# ddr3.net
KiCad netlist of a schematic drawn in Altium Designer
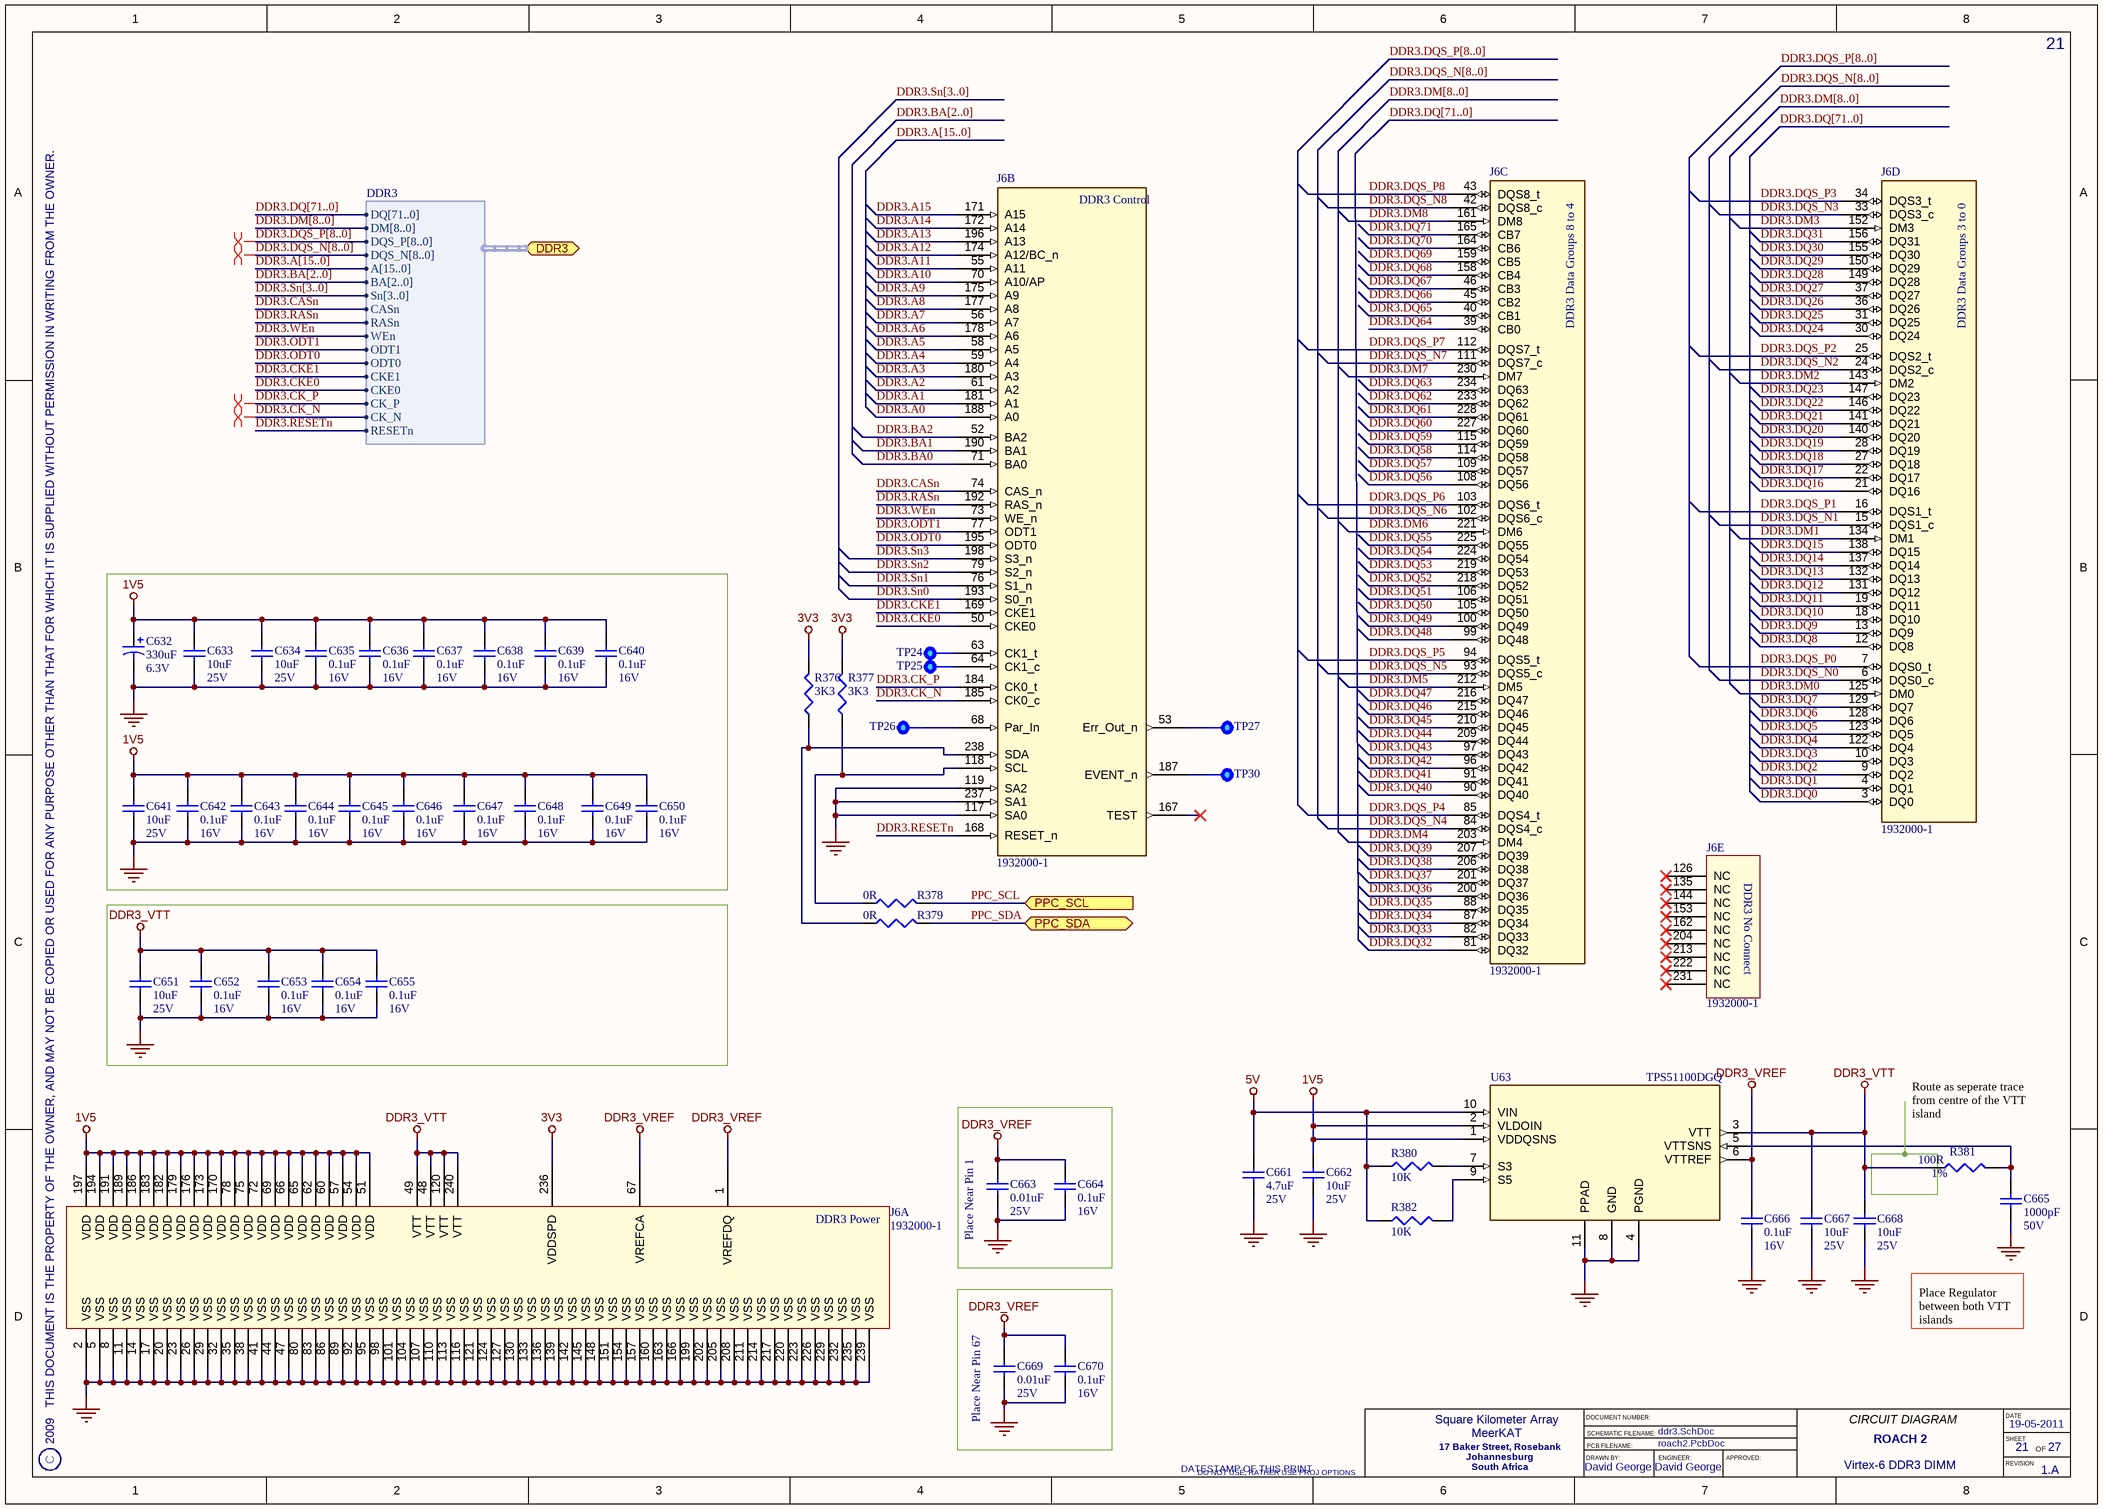
[diagram p0: ddr3.SchDoc]

(export (version "E")
  (design (tool "Eeschema 10.0.6"))
  (components
    (comp (ref "C632")
      (value "330uF")
      (footprint "CAPMP7343X280L")
      (description "330uF, Conductive Polymer Chip Capacitor")
      (fields
        (field (name "RATING") "6.3V")
        (field (name "MANUFACTURER") "KEMET")
        (field (name "PARTNUM") "T520D337M006ATE045")
      )
      (libsource (lib "altium_db") (part "CapPol"))
    )
    (comp (ref "C633")
      (value "10uF")
      (footprint "CAPC3225X200L")
      (description "10uF, Ceramic Capacitor")
      (fields
        (field (name "RATING") "25V")
        (field (name "MANUFACTURER") "MURATA")
        (field (name "PARTNUM") "GRM32DR61E106KA12L")
      )
      (libsource (lib "altium_db") (part "CapStd"))
    )
    (comp (ref "C634")
      (value "10uF")
      (footprint "CAPC3225X200L")
      (description "10uF, Ceramic Capacitor")
      (fields
        (field (name "RATING") "25V")
        (field (name "MANUFACTURER") "MURATA")
        (field (name "PARTNUM") "GRM32DR61E106KA12L")
      )
      (libsource (lib "altium_db") (part "CapStd"))
    )
    (comp (ref "C635")
      (value "0.1uF")
      (footprint "CAPC1005X60L")
      (description "0.1uF, Ceramic Capacitor")
      (fields
        (field (name "RATING") "16V")
        (field (name "MANUFACTURER") "VENKEL")
        (field (name "PARTNUM") "C0402X7R160-104KN")
      )
      (libsource (lib "altium_db") (part "CapStd"))
    )
    (comp (ref "C636")
      (value "0.1uF")
      (footprint "CAPC1005X60L")
      (description "0.1uF, Ceramic Capacitor")
      (fields
        (field (name "RATING") "16V")
        (field (name "MANUFACTURER") "VENKEL")
        (field (name "PARTNUM") "C0402X7R160-104KN")
      )
      (libsource (lib "altium_db") (part "CapStd"))
    )
    (comp (ref "C637")
      (value "0.1uF")
      (footprint "CAPC1005X60L")
      (description "0.1uF, Ceramic Capacitor")
      (fields
        (field (name "RATING") "16V")
        (field (name "MANUFACTURER") "VENKEL")
        (field (name "PARTNUM") "C0402X7R160-104KN")
      )
      (libsource (lib "altium_db") (part "CapStd"))
    )
    (comp (ref "C638")
      (value "0.1uF")
      (footprint "CAPC1005X60L")
      (description "0.1uF, Ceramic Capacitor")
      (fields
        (field (name "RATING") "16V")
        (field (name "MANUFACTURER") "VENKEL")
        (field (name "PARTNUM") "C0402X7R160-104KN")
      )
      (libsource (lib "altium_db") (part "CapStd"))
    )
    (comp (ref "C639")
      (value "0.1uF")
      (footprint "CAPC1005X60L")
      (description "0.1uF, Ceramic Capacitor")
      (fields
        (field (name "RATING") "16V")
        (field (name "MANUFACTURER") "VENKEL")
        (field (name "PARTNUM") "C0402X7R160-104KN")
      )
      (libsource (lib "altium_db") (part "CapStd"))
    )
    (comp (ref "C640")
      (value "0.1uF")
      (footprint "CAPC1005X60L")
      (description "0.1uF, Ceramic Capacitor")
      (fields
        (field (name "RATING") "16V")
        (field (name "MANUFACTURER") "VENKEL")
        (field (name "PARTNUM") "C0402X7R160-104KN")
      )
      (libsource (lib "altium_db") (part "CapStd"))
    )
    (comp (ref "C641")
      (value "10uF")
      (footprint "CAPC3225X200L")
      (description "10uF, Ceramic Capacitor")
      (fields
        (field (name "RATING") "25V")
        (field (name "MANUFACTURER") "MURATA")
        (field (name "PARTNUM") "GRM32DR61E106KA12L")
      )
      (libsource (lib "altium_db") (part "CapStd"))
    )
    (comp (ref "C642")
      (value "0.1uF")
      (footprint "CAPC1005X60L")
      (description "0.1uF, Ceramic Capacitor")
      (fields
        (field (name "RATING") "16V")
        (field (name "MANUFACTURER") "VENKEL")
        (field (name "PARTNUM") "C0402X7R160-104KN")
      )
      (libsource (lib "altium_db") (part "CapStd"))
    )
    (comp (ref "C643")
      (value "0.1uF")
      (footprint "CAPC1005X60L")
      (description "0.1uF, Ceramic Capacitor")
      (fields
        (field (name "RATING") "16V")
        (field (name "MANUFACTURER") "VENKEL")
        (field (name "PARTNUM") "C0402X7R160-104KN")
      )
      (libsource (lib "altium_db") (part "CapStd"))
    )
    (comp (ref "C644")
      (value "0.1uF")
      (footprint "CAPC1005X60L")
      (description "0.1uF, Ceramic Capacitor")
      (fields
        (field (name "RATING") "16V")
        (field (name "MANUFACTURER") "VENKEL")
        (field (name "PARTNUM") "C0402X7R160-104KN")
      )
      (libsource (lib "altium_db") (part "CapStd"))
    )
    (comp (ref "C645")
      (value "0.1uF")
      (footprint "CAPC1005X60L")
      (description "0.1uF, Ceramic Capacitor")
      (fields
        (field (name "RATING") "16V")
        (field (name "MANUFACTURER") "VENKEL")
        (field (name "PARTNUM") "C0402X7R160-104KN")
      )
      (libsource (lib "altium_db") (part "CapStd"))
    )
    (comp (ref "C646")
      (value "0.1uF")
      (footprint "CAPC1005X60L")
      (description "0.1uF, Ceramic Capacitor")
      (fields
        (field (name "RATING") "16V")
        (field (name "MANUFACTURER") "VENKEL")
        (field (name "PARTNUM") "C0402X7R160-104KN")
      )
      (libsource (lib "altium_db") (part "CapStd"))
    )
    (comp (ref "C647")
      (value "0.1uF")
      (footprint "CAPC1005X60L")
      (description "0.1uF, Ceramic Capacitor")
      (fields
        (field (name "RATING") "16V")
        (field (name "MANUFACTURER") "VENKEL")
        (field (name "PARTNUM") "C0402X7R160-104KN")
      )
      (libsource (lib "altium_db") (part "CapStd"))
    )
    (comp (ref "C648")
      (value "0.1uF")
      (footprint "CAPC1005X60L")
      (description "0.1uF, Ceramic Capacitor")
      (fields
        (field (name "RATING") "16V")
        (field (name "MANUFACTURER") "VENKEL")
        (field (name "PARTNUM") "C0402X7R160-104KN")
      )
      (libsource (lib "altium_db") (part "CapStd"))
    )
    (comp (ref "C649")
      (value "0.1uF")
      (footprint "CAPC1005X60L")
      (description "0.1uF, Ceramic Capacitor")
      (fields
        (field (name "RATING") "16V")
        (field (name "MANUFACTURER") "VENKEL")
        (field (name "PARTNUM") "C0402X7R160-104KN")
      )
      (libsource (lib "altium_db") (part "CapStd"))
    )
    (comp (ref "C650")
      (value "0.1uF")
      (footprint "CAPC1005X60L")
      (description "0.1uF, Ceramic Capacitor")
      (fields
        (field (name "RATING") "16V")
        (field (name "MANUFACTURER") "VENKEL")
        (field (name "PARTNUM") "C0402X7R160-104KN")
      )
      (libsource (lib "altium_db") (part "CapStd"))
    )
    (comp (ref "C651")
      (value "10uF")
      (footprint "CAPC3225X200L")
      (description "10uF, Ceramic Capacitor")
      (fields
        (field (name "RATING") "25V")
        (field (name "MANUFACTURER") "MURATA")
        (field (name "PARTNUM") "GRM32DR61E106KA12L")
      )
      (libsource (lib "altium_db") (part "CapStd"))
    )
    (comp (ref "C652")
      (value "0.1uF")
      (footprint "CAPC1005X60L")
      (description "0.1uF, Ceramic Capacitor")
      (fields
        (field (name "RATING") "16V")
        (field (name "MANUFACTURER") "VENKEL")
        (field (name "PARTNUM") "C0402X7R160-104KN")
      )
      (libsource (lib "altium_db") (part "CapStd"))
    )
    (comp (ref "C653")
      (value "0.1uF")
      (footprint "CAPC1005X60L")
      (description "0.1uF, Ceramic Capacitor")
      (fields
        (field (name "RATING") "16V")
        (field (name "MANUFACTURER") "VENKEL")
        (field (name "PARTNUM") "C0402X7R160-104KN")
      )
      (libsource (lib "altium_db") (part "CapStd"))
    )
    (comp (ref "C654")
      (value "0.1uF")
      (footprint "CAPC1005X60L")
      (description "0.1uF, Ceramic Capacitor")
      (fields
        (field (name "RATING") "16V")
        (field (name "MANUFACTURER") "VENKEL")
        (field (name "PARTNUM") "C0402X7R160-104KN")
      )
      (libsource (lib "altium_db") (part "CapStd"))
    )
    (comp (ref "C655")
      (value "0.1uF")
      (footprint "CAPC1005X60L")
      (description "0.1uF, Ceramic Capacitor")
      (fields
        (field (name "RATING") "16V")
        (field (name "MANUFACTURER") "VENKEL")
        (field (name "PARTNUM") "C0402X7R160-104KN")
      )
      (libsource (lib "altium_db") (part "CapStd"))
    )
    (comp (ref "C661")
      (value "4.7uF")
      (footprint "CAPC2012X127L")
      (description "4.7uF, Ceramic Capacitor")
      (fields
        (field (name "RATING") "25V")
        (field (name "MANUFACTURER") "MURATA")
        (field (name "PARTNUM") "GRM21BR61E475KA12K")
      )
      (libsource (lib "altium_db") (part "CapStd"))
    )
    (comp (ref "C662")
      (value "10uF")
      (footprint "CAPC3225X200L")
      (description "10uF, Ceramic Capacitor")
      (fields
        (field (name "RATING") "25V")
        (field (name "MANUFACTURER") "MURATA")
        (field (name "PARTNUM") "GRM32DR61E106KA12L")
      )
      (libsource (lib "altium_db") (part "CapStd"))
    )
    (comp (ref "C663")
      (value "0.01uF")
      (footprint "CAPC1005X55L")
      (description "0.01uF, Ceramic Capacitor")
      (fields
        (field (name "RATING") "25V")
        (field (name "MANUFACTURER") "MURATA")
        (field (name "PARTNUM") "GRM155R71E103KA01D")
      )
      (libsource (lib "altium_db") (part "CapStd"))
    )
    (comp (ref "C664")
      (value "0.1uF")
      (footprint "CAPC1005X60L")
      (description "0.1uF, Ceramic Capacitor")
      (fields
        (field (name "RATING") "16V")
        (field (name "MANUFACTURER") "VENKEL")
        (field (name "PARTNUM") "C0402X7R160-104KN")
      )
      (libsource (lib "altium_db") (part "CapStd"))
    )
    (comp (ref "C665")
      (value "1000pF")
      (footprint "CAPC1005X55L")
      (description "1000pF, Ceramic Capacitor")
      (fields
        (field (name "RATING") "50V")
        (field (name "MANUFACTURER") "MURATA")
        (field (name "PARTNUM") "GRM155R61H102KA01D")
      )
      (libsource (lib "altium_db") (part "CapStd"))
    )
    (comp (ref "C666")
      (value "0.1uF")
      (footprint "CAPC1005X60L")
      (description "0.1uF, Ceramic Capacitor")
      (fields
        (field (name "RATING") "16V")
        (field (name "MANUFACTURER") "VENKEL")
        (field (name "PARTNUM") "C0402X7R160-104KN")
      )
      (libsource (lib "altium_db") (part "CapStd"))
    )
    (comp (ref "C667")
      (value "10uF")
      (footprint "CAPC3225X200L")
      (description "10uF, Ceramic Capacitor")
      (fields
        (field (name "RATING") "25V")
        (field (name "MANUFACTURER") "MURATA")
        (field (name "PARTNUM") "GRM32DR61E106KA12L")
      )
      (libsource (lib "altium_db") (part "CapStd"))
    )
    (comp (ref "C668")
      (value "10uF")
      (footprint "CAPC3225X200L")
      (description "10uF, Ceramic Capacitor")
      (fields
        (field (name "RATING") "25V")
        (field (name "MANUFACTURER") "MURATA")
        (field (name "PARTNUM") "GRM32DR61E106KA12L")
      )
      (libsource (lib "altium_db") (part "CapStd"))
    )
    (comp (ref "C669")
      (value "0.01uF")
      (footprint "CAPC1005X55L")
      (description "0.01uF, Ceramic Capacitor")
      (fields
        (field (name "RATING") "25V")
        (field (name "MANUFACTURER") "MURATA")
        (field (name "PARTNUM") "GRM155R71E103KA01D")
      )
      (libsource (lib "altium_db") (part "CapStd"))
    )
    (comp (ref "C670")
      (value "0.1uF")
      (footprint "CAPC1005X60L")
      (description "0.1uF, Ceramic Capacitor")
      (fields
        (field (name "RATING") "16V")
        (field (name "MANUFACTURER") "VENKEL")
        (field (name "PARTNUM") "C0402X7R160-104KN")
      )
      (libsource (lib "altium_db") (part "CapStd"))
    )
    (comp (ref "J6")
      (value "1932000-1")
      (footprint "TYCO_1932000-1")
      (description "240-pin DDR3 DIMM Socket")
      (fields (field (name "PARTNUM") "1932000-1") (field (name "MANUFACTURER") "TYCO"))
      (libsource (lib "altium_db") (part "ddr3_dimm_240"))
    )
    (comp (ref "R376")
      (value "3K3")
      (footprint "RESC1005X40L")
      (description "3K3, 1.1mm x 0.5mm, Thick Film Resistor")
      (fields (field (name "MANUFACTURER") "ROYALOHM") (field (name "PARTNUM") "0402WGJ0332T1E"))
      (libsource (lib "altium_db") (part "ResStd"))
    )
    (comp (ref "R377")
      (value "3K3")
      (footprint "RESC1005X40L")
      (description "3K3, 1.1mm x 0.5mm, Thick Film Resistor")
      (fields (field (name "MANUFACTURER") "ROYALOHM") (field (name "PARTNUM") "0402WGJ0332T1E"))
      (libsource (lib "altium_db") (part "ResStd"))
    )
    (comp (ref "R378")
      (value "0R")
      (footprint "RESC1005X40L")
      (description "0R, 1.1mm x 0.5mm, Thick Film Resistor")
      (fields (field (name "MANUFACTURER") "ROYALOHM") (field (name "PARTNUM") "0402WG00000T1E"))
      (libsource (lib "altium_db") (part "ResStd"))
    )
    (comp (ref "R379")
      (value "0R")
      (footprint "RESC1005X40L")
      (description "0R, 1.1mm x 0.5mm, Thick Film Resistor")
      (fields (field (name "MANUFACTURER") "ROYALOHM") (field (name "PARTNUM") "0402WG00000T1E"))
      (libsource (lib "altium_db") (part "ResStd"))
    )
    (comp (ref "R380")
      (value "10K")
      (footprint "RESC1005X40L")
      (description "10K, 1.1mm x 0.5mm, Thick Film Resistor")
      (fields (field (name "MANUFACTURER") "ROYALOHM") (field (name "PARTNUM") "0402WGJ0103T1E"))
      (libsource (lib "altium_db") (part "ResStd"))
    )
    (comp (ref "R381")
      (value "100R")
      (footprint "RESC1005X40L")
      (description "100R, 1.1mm x 0.5mm, Thick Film Resistor")
      (fields
        (field (name "MANUFACTURER") "ROYALOHM")
        (field (name "PARTNUM") "0402WGF0101T1E")
        (field (name "TOLERANCE") "1%")
      )
      (libsource (lib "altium_db") (part "ResStd"))
    )
    (comp (ref "R382")
      (value "10K")
      (footprint "RESC1005X40L")
      (description "10K, 1.1mm x 0.5mm, Thick Film Resistor")
      (fields (field (name "MANUFACTURER") "ROYALOHM") (field (name "PARTNUM") "0402WGJ0103T1E"))
      (libsource (lib "altium_db") (part "ResStd"))
    )
    (comp (ref "TP24")
      (value "Testpoint")
      (footprint "TP100")
      (description "1mm Diameter, through-hole, Circular Test-point")
      (libsource (lib "altium_db") (part "Testpoint"))
    )
    (comp (ref "TP25")
      (value "Testpoint")
      (footprint "TP100")
      (description "1mm Diameter, through-hole, Circular Test-point")
      (libsource (lib "altium_db") (part "Testpoint"))
    )
    (comp (ref "TP26")
      (value "Testpoint")
      (footprint "TP100")
      (description "1mm Diameter, through-hole, Circular Test-point")
      (libsource (lib "altium_db") (part "Testpoint"))
    )
    (comp (ref "TP27")
      (value "Testpoint")
      (footprint "TP100")
      (description "1mm Diameter, through-hole, Circular Test-point")
      (libsource (lib "altium_db") (part "Testpoint"))
    )
    (comp (ref "TP30")
      (value "Testpoint")
      (footprint "TP100")
      (description "1mm Diameter, through-hole, Circular Test-point")
      (libsource (lib "altium_db") (part "Testpoint"))
    )
    (comp (ref "U63")
      (value "TPS51100DGQ")
      (footprint "MSOP_10-N")
      (description "3A Sink/Source Regulator")
      (fields (field (name "MANUFACTURER") "Texas Instruments"))
      (libsource (lib "altium_db") (part "TPS51100DGQ"))
    )
  )
  (nets
    (net (code "2") (name "/DDR3.A0") (class "Default")
      (node (ref "J6") (pin "188") (pinfunction "A0_188") (pintype "input"))
    )
    (net (code "3") (name "/DDR3.A1") (class "Default")
      (node (ref "J6") (pin "181") (pinfunction "A1_181") (pintype "input"))
    )
    (net (code "4") (name "/DDR3.A2") (class "Default")
      (node (ref "J6") (pin "61") (pinfunction "A2_61") (pintype "input"))
    )
    (net (code "5") (name "/DDR3.A3") (class "Default")
      (node (ref "J6") (pin "180") (pinfunction "A3_180") (pintype "input"))
    )
    (net (code "6") (name "/DDR3.A4") (class "Default")
      (node (ref "J6") (pin "59") (pinfunction "A4_59") (pintype "input"))
    )
    (net (code "7") (name "/DDR3.A5") (class "Default")
      (node (ref "J6") (pin "58") (pinfunction "A5_58") (pintype "input"))
    )
    (net (code "8") (name "/DDR3.A6") (class "Default")
      (node (ref "J6") (pin "178") (pinfunction "A6_178") (pintype "input"))
    )
    (net (code "9") (name "/DDR3.A7") (class "Default")
      (node (ref "J6") (pin "56") (pinfunction "A7_56") (pintype "input"))
    )
    (net (code "10") (name "/DDR3.A8") (class "Default")
      (node (ref "J6") (pin "177") (pinfunction "A8_177") (pintype "input"))
    )
    (net (code "11") (name "/DDR3.A9") (class "Default")
      (node (ref "J6") (pin "175") (pinfunction "A9_175") (pintype "input"))
    )
    (net (code "12") (name "/DDR3.A10") (class "Default")
      (node (ref "J6") (pin "70") (pinfunction "A10/AP_70") (pintype "input"))
    )
    (net (code "13") (name "/DDR3.A11") (class "Default")
      (node (ref "J6") (pin "55") (pinfunction "A11_55") (pintype "input"))
    )
    (net (code "14") (name "/DDR3.A12") (class "Default")
      (node (ref "J6") (pin "174") (pinfunction "A12/BC_n_174") (pintype "input"))
    )
    (net (code "15") (name "/DDR3.A13") (class "Default")
      (node (ref "J6") (pin "196") (pinfunction "A13_196") (pintype "input"))
    )
    (net (code "16") (name "/DDR3.A14") (class "Default")
      (node (ref "J6") (pin "172") (pinfunction "A14_172") (pintype "input"))
    )
    (net (code "17") (name "/DDR3.A15") (class "Default")
      (node (ref "J6") (pin "171") (pinfunction "A15_171") (pintype "input"))
    )
    (net (code "19") (name "/DDR3.BA0") (class "Default")
      (node (ref "J6") (pin "71") (pinfunction "BA0_71") (pintype "input"))
    )
    (net (code "20") (name "/DDR3.BA1") (class "Default")
      (node (ref "J6") (pin "190") (pinfunction "BA1_190") (pintype "input"))
    )
    (net (code "21") (name "/DDR3.BA2") (class "Default")
      (node (ref "J6") (pin "52") (pinfunction "BA2_52") (pintype "input"))
    )
    (net (code "23") (name "/DDR3.CASn") (class "Default")
      (node (ref "J6") (pin "74") (pinfunction "CAS_n_74") (pintype "input"))
    )
    (net (code "24") (name "/DDR3.CKE0") (class "Default")
      (node (ref "J6") (pin "50") (pinfunction "CKE0_50") (pintype "input"))
    )
    (net (code "25") (name "/DDR3.CKE1") (class "Default")
      (node (ref "J6") (pin "169") (pinfunction "CKE1_169") (pintype "input"))
    )
    (net (code "26") (name "/DDR3.CK_N") (class "Default")
      (node (ref "J6") (pin "185") (pinfunction "CK0_c_185") (pintype "input"))
    )
    (net (code "27") (name "/DDR3.CK_P") (class "Default")
      (node (ref "J6") (pin "184") (pinfunction "CK0_t_184") (pintype "input"))
    )
    (net (code "28") (name "/DDR3.DM0") (class "Default")
      (node (ref "J6") (pin "125") (pinfunction "DM0_125") (pintype "input"))
    )
    (net (code "29") (name "/DDR3.DM1") (class "Default")
      (node (ref "J6") (pin "134") (pinfunction "DM1_134") (pintype "input"))
    )
    (net (code "30") (name "/DDR3.DM2") (class "Default")
      (node (ref "J6") (pin "143") (pinfunction "DM2_143") (pintype "input"))
    )
    (net (code "31") (name "/DDR3.DM3") (class "Default")
      (node (ref "J6") (pin "152") (pinfunction "DM3_152") (pintype "input"))
    )
    (net (code "32") (name "/DDR3.DM4") (class "Default")
      (node (ref "J6") (pin "203") (pinfunction "DM4_203") (pintype "input"))
    )
    (net (code "33") (name "/DDR3.DM5") (class "Default")
      (node (ref "J6") (pin "212") (pinfunction "DM5_212") (pintype "input"))
    )
    (net (code "34") (name "/DDR3.DM6") (class "Default")
      (node (ref "J6") (pin "221") (pinfunction "DM6_221") (pintype "input"))
    )
    (net (code "35") (name "/DDR3.DM7") (class "Default")
      (node (ref "J6") (pin "230") (pinfunction "DM7_230") (pintype "input"))
    )
    (net (code "36") (name "/DDR3.DM8") (class "Default")
      (node (ref "J6") (pin "161") (pinfunction "DM8_161") (pintype "input"))
    )
    (net (code "38") (name "/DDR3.DQ0") (class "Default")
      (node (ref "J6") (pin "3") (pinfunction "DQ0_3") (pintype "bidirectional"))
    )
    (net (code "39") (name "/DDR3.DQ1") (class "Default")
      (node (ref "J6") (pin "4") (pinfunction "DQ1_4") (pintype "bidirectional"))
    )
    (net (code "40") (name "/DDR3.DQ2") (class "Default")
      (node (ref "J6") (pin "9") (pinfunction "DQ2_9") (pintype "bidirectional"))
    )
    (net (code "41") (name "/DDR3.DQ3") (class "Default")
      (node (ref "J6") (pin "10") (pinfunction "DQ3_10") (pintype "bidirectional"))
    )
    (net (code "42") (name "/DDR3.DQ4") (class "Default")
      (node (ref "J6") (pin "122") (pinfunction "DQ4_122") (pintype "bidirectional"))
    )
    (net (code "43") (name "/DDR3.DQ5") (class "Default")
      (node (ref "J6") (pin "123") (pinfunction "DQ5_123") (pintype "bidirectional"))
    )
    (net (code "44") (name "/DDR3.DQ6") (class "Default")
      (node (ref "J6") (pin "128") (pinfunction "DQ6_128") (pintype "bidirectional"))
    )
    (net (code "45") (name "/DDR3.DQ7") (class "Default")
      (node (ref "J6") (pin "129") (pinfunction "DQ7_129") (pintype "bidirectional"))
    )
    (net (code "46") (name "/DDR3.DQ8") (class "Default")
      (node (ref "J6") (pin "12") (pinfunction "DQ8_12") (pintype "bidirectional"))
    )
    (net (code "47") (name "/DDR3.DQ9") (class "Default")
      (node (ref "J6") (pin "13") (pinfunction "DQ9_13") (pintype "bidirectional"))
    )
    (net (code "48") (name "/DDR3.DQ10") (class "Default")
      (node (ref "J6") (pin "18") (pinfunction "DQ10_18") (pintype "bidirectional"))
    )
    (net (code "49") (name "/DDR3.DQ11") (class "Default")
      (node (ref "J6") (pin "19") (pinfunction "DQ11_19") (pintype "bidirectional"))
    )
    (net (code "50") (name "/DDR3.DQ12") (class "Default")
      (node (ref "J6") (pin "131") (pinfunction "DQ12_131") (pintype "bidirectional"))
    )
    (net (code "51") (name "/DDR3.DQ13") (class "Default")
      (node (ref "J6") (pin "132") (pinfunction "DQ13_132") (pintype "bidirectional"))
    )
    (net (code "52") (name "/DDR3.DQ14") (class "Default")
      (node (ref "J6") (pin "137") (pinfunction "DQ14_137") (pintype "bidirectional"))
    )
    (net (code "53") (name "/DDR3.DQ15") (class "Default")
      (node (ref "J6") (pin "138") (pinfunction "DQ15_138") (pintype "bidirectional"))
    )
    (net (code "54") (name "/DDR3.DQ16") (class "Default")
      (node (ref "J6") (pin "21") (pinfunction "DQ16_21") (pintype "bidirectional"))
    )
    (net (code "55") (name "/DDR3.DQ17") (class "Default")
      (node (ref "J6") (pin "22") (pinfunction "DQ17_22") (pintype "bidirectional"))
    )
    (net (code "56") (name "/DDR3.DQ18") (class "Default")
      (node (ref "J6") (pin "27") (pinfunction "DQ18_27") (pintype "bidirectional"))
    )
    (net (code "57") (name "/DDR3.DQ19") (class "Default")
      (node (ref "J6") (pin "28") (pinfunction "DQ19_28") (pintype "bidirectional"))
    )
    (net (code "58") (name "/DDR3.DQ20") (class "Default")
      (node (ref "J6") (pin "140") (pinfunction "DQ20_140") (pintype "bidirectional"))
    )
    (net (code "59") (name "/DDR3.DQ21") (class "Default")
      (node (ref "J6") (pin "141") (pinfunction "DQ21_141") (pintype "bidirectional"))
    )
    (net (code "60") (name "/DDR3.DQ22") (class "Default")
      (node (ref "J6") (pin "146") (pinfunction "DQ22_146") (pintype "bidirectional"))
    )
    (net (code "61") (name "/DDR3.DQ23") (class "Default")
      (node (ref "J6") (pin "147") (pinfunction "DQ23_147") (pintype "bidirectional"))
    )
    (net (code "62") (name "/DDR3.DQ24") (class "Default")
      (node (ref "J6") (pin "30") (pinfunction "DQ24_30") (pintype "bidirectional"))
    )
    (net (code "63") (name "/DDR3.DQ25") (class "Default")
      (node (ref "J6") (pin "31") (pinfunction "DQ25_31") (pintype "bidirectional"))
    )
    (net (code "64") (name "/DDR3.DQ26") (class "Default")
      (node (ref "J6") (pin "36") (pinfunction "DQ26_36") (pintype "bidirectional"))
    )
    (net (code "65") (name "/DDR3.DQ27") (class "Default")
      (node (ref "J6") (pin "37") (pinfunction "DQ27_37") (pintype "bidirectional"))
    )
    (net (code "66") (name "/DDR3.DQ28") (class "Default")
      (node (ref "J6") (pin "149") (pinfunction "DQ28_149") (pintype "bidirectional"))
    )
    (net (code "67") (name "/DDR3.DQ29") (class "Default")
      (node (ref "J6") (pin "150") (pinfunction "DQ29_150") (pintype "bidirectional"))
    )
    (net (code "68") (name "/DDR3.DQ30") (class "Default")
      (node (ref "J6") (pin "155") (pinfunction "DQ30_155") (pintype "bidirectional"))
    )
    (net (code "69") (name "/DDR3.DQ31") (class "Default")
      (node (ref "J6") (pin "156") (pinfunction "DQ31_156") (pintype "bidirectional"))
    )
    (net (code "70") (name "/DDR3.DQ32") (class "Default")
      (node (ref "J6") (pin "81") (pinfunction "DQ32_81") (pintype "bidirectional"))
    )
    (net (code "71") (name "/DDR3.DQ33") (class "Default")
      (node (ref "J6") (pin "82") (pinfunction "DQ33_82") (pintype "bidirectional"))
    )
    (net (code "72") (name "/DDR3.DQ34") (class "Default")
      (node (ref "J6") (pin "87") (pinfunction "DQ34_87") (pintype "bidirectional"))
    )
    (net (code "73") (name "/DDR3.DQ35") (class "Default")
      (node (ref "J6") (pin "88") (pinfunction "DQ35_88") (pintype "bidirectional"))
    )
    (net (code "74") (name "/DDR3.DQ36") (class "Default")
      (node (ref "J6") (pin "200") (pinfunction "DQ36_200") (pintype "bidirectional"))
    )
    (net (code "75") (name "/DDR3.DQ37") (class "Default")
      (node (ref "J6") (pin "201") (pinfunction "DQ37_201") (pintype "bidirectional"))
    )
    (net (code "76") (name "/DDR3.DQ38") (class "Default")
      (node (ref "J6") (pin "206") (pinfunction "DQ38_206") (pintype "bidirectional"))
    )
    (net (code "77") (name "/DDR3.DQ39") (class "Default")
      (node (ref "J6") (pin "207") (pinfunction "DQ39_207") (pintype "bidirectional"))
    )
    (net (code "78") (name "/DDR3.DQ40") (class "Default")
      (node (ref "J6") (pin "90") (pinfunction "DQ40_90") (pintype "bidirectional"))
    )
    (net (code "79") (name "/DDR3.DQ41") (class "Default")
      (node (ref "J6") (pin "91") (pinfunction "DQ41_91") (pintype "bidirectional"))
    )
    (net (code "80") (name "/DDR3.DQ42") (class "Default")
      (node (ref "J6") (pin "96") (pinfunction "DQ42_96") (pintype "bidirectional"))
    )
    (net (code "81") (name "/DDR3.DQ43") (class "Default")
      (node (ref "J6") (pin "97") (pinfunction "DQ43_97") (pintype "bidirectional"))
    )
    (net (code "82") (name "/DDR3.DQ44") (class "Default")
      (node (ref "J6") (pin "209") (pinfunction "DQ44_209") (pintype "bidirectional"))
    )
    (net (code "83") (name "/DDR3.DQ45") (class "Default")
      (node (ref "J6") (pin "210") (pinfunction "DQ45_210") (pintype "bidirectional"))
    )
    (net (code "84") (name "/DDR3.DQ46") (class "Default")
      (node (ref "J6") (pin "215") (pinfunction "DQ46_215") (pintype "bidirectional"))
    )
    (net (code "85") (name "/DDR3.DQ47") (class "Default")
      (node (ref "J6") (pin "216") (pinfunction "DQ47_216") (pintype "bidirectional"))
    )
    (net (code "86") (name "/DDR3.DQ48") (class "Default")
      (node (ref "J6") (pin "99") (pinfunction "DQ48_99") (pintype "bidirectional"))
    )
    (net (code "87") (name "/DDR3.DQ49") (class "Default")
      (node (ref "J6") (pin "100") (pinfunction "DQ49_100") (pintype "bidirectional"))
    )
    (net (code "88") (name "/DDR3.DQ50") (class "Default")
      (node (ref "J6") (pin "105") (pinfunction "DQ50_105") (pintype "bidirectional"))
    )
    (net (code "89") (name "/DDR3.DQ51") (class "Default")
      (node (ref "J6") (pin "106") (pinfunction "DQ51_106") (pintype "bidirectional"))
    )
    (net (code "90") (name "/DDR3.DQ52") (class "Default")
      (node (ref "J6") (pin "218") (pinfunction "DQ52_218") (pintype "bidirectional"))
    )
    (net (code "91") (name "/DDR3.DQ53") (class "Default")
      (node (ref "J6") (pin "219") (pinfunction "DQ53_219") (pintype "bidirectional"))
    )
    (net (code "92") (name "/DDR3.DQ54") (class "Default")
      (node (ref "J6") (pin "224") (pinfunction "DQ54_224") (pintype "bidirectional"))
    )
    (net (code "93") (name "/DDR3.DQ55") (class "Default")
      (node (ref "J6") (pin "225") (pinfunction "DQ55_225") (pintype "bidirectional"))
    )
    (net (code "94") (name "/DDR3.DQ56") (class "Default")
      (node (ref "J6") (pin "108") (pinfunction "DQ56_108") (pintype "bidirectional"))
    )
    (net (code "95") (name "/DDR3.DQ57") (class "Default")
      (node (ref "J6") (pin "109") (pinfunction "DQ57_109") (pintype "bidirectional"))
    )
    (net (code "96") (name "/DDR3.DQ58") (class "Default")
      (node (ref "J6") (pin "114") (pinfunction "DQ58_114") (pintype "bidirectional"))
    )
    (net (code "97") (name "/DDR3.DQ59") (class "Default")
      (node (ref "J6") (pin "115") (pinfunction "DQ59_115") (pintype "bidirectional"))
    )
    (net (code "98") (name "/DDR3.DQ60") (class "Default")
      (node (ref "J6") (pin "227") (pinfunction "DQ60_227") (pintype "bidirectional"))
    )
    (net (code "99") (name "/DDR3.DQ61") (class "Default")
      (node (ref "J6") (pin "228") (pinfunction "DQ61_228") (pintype "bidirectional"))
    )
    (net (code "100") (name "/DDR3.DQ62") (class "Default")
      (node (ref "J6") (pin "233") (pinfunction "DQ62_233") (pintype "bidirectional"))
    )
    (net (code "101") (name "/DDR3.DQ63") (class "Default")
      (node (ref "J6") (pin "234") (pinfunction "DQ63_234") (pintype "bidirectional"))
    )
    (net (code "102") (name "/DDR3.DQ64") (class "Default")
      (node (ref "J6") (pin "39") (pinfunction "CB0_39") (pintype "bidirectional"))
    )
    (net (code "103") (name "/DDR3.DQ65") (class "Default")
      (node (ref "J6") (pin "40") (pinfunction "CB1_40") (pintype "bidirectional"))
    )
    (net (code "104") (name "/DDR3.DQ66") (class "Default")
      (node (ref "J6") (pin "45") (pinfunction "CB2_45") (pintype "bidirectional"))
    )
    (net (code "105") (name "/DDR3.DQ67") (class "Default")
      (node (ref "J6") (pin "46") (pinfunction "CB3_46") (pintype "bidirectional"))
    )
    (net (code "106") (name "/DDR3.DQ68") (class "Default")
      (node (ref "J6") (pin "158") (pinfunction "CB4_158") (pintype "bidirectional"))
    )
    (net (code "107") (name "/DDR3.DQ69") (class "Default")
      (node (ref "J6") (pin "159") (pinfunction "CB5_159") (pintype "bidirectional"))
    )
    (net (code "108") (name "/DDR3.DQ70") (class "Default")
      (node (ref "J6") (pin "164") (pinfunction "CB6_164") (pintype "bidirectional"))
    )
    (net (code "109") (name "/DDR3.DQ71") (class "Default")
      (node (ref "J6") (pin "165") (pinfunction "CB7_165") (pintype "bidirectional"))
    )
    (net (code "110") (name "/DDR3.DQS_N0") (class "Default")
      (node (ref "J6") (pin "6") (pinfunction "DQS0_c_6") (pintype "bidirectional"))
    )
    (net (code "111") (name "/DDR3.DQS_N1") (class "Default")
      (node (ref "J6") (pin "15") (pinfunction "DQS1_c_15") (pintype "bidirectional"))
    )
    (net (code "112") (name "/DDR3.DQS_N2") (class "Default")
      (node (ref "J6") (pin "24") (pinfunction "DQS2_c_24") (pintype "bidirectional"))
    )
    (net (code "113") (name "/DDR3.DQS_N3") (class "Default")
      (node (ref "J6") (pin "33") (pinfunction "DQS3_c_33") (pintype "bidirectional"))
    )
    (net (code "114") (name "/DDR3.DQS_N4") (class "Default")
      (node (ref "J6") (pin "84") (pinfunction "DQS4_c_84") (pintype "bidirectional"))
    )
    (net (code "115") (name "/DDR3.DQS_N5") (class "Default")
      (node (ref "J6") (pin "93") (pinfunction "DQS5_c_93") (pintype "bidirectional"))
    )
    (net (code "116") (name "/DDR3.DQS_N6") (class "Default")
      (node (ref "J6") (pin "102") (pinfunction "DQS6_c_102") (pintype "bidirectional"))
    )
    (net (code "117") (name "/DDR3.DQS_N7") (class "Default")
      (node (ref "J6") (pin "111") (pinfunction "DQS7_c_111") (pintype "bidirectional"))
    )
    (net (code "118") (name "/DDR3.DQS_N8") (class "Default")
      (node (ref "J6") (pin "42") (pinfunction "DQS8_c_42") (pintype "bidirectional"))
    )
    (net (code "120") (name "/DDR3.DQS_P0") (class "Default")
      (node (ref "J6") (pin "7") (pinfunction "DQS0_t_7") (pintype "bidirectional"))
    )
    (net (code "121") (name "/DDR3.DQS_P1") (class "Default")
      (node (ref "J6") (pin "16") (pinfunction "DQS1_t_16") (pintype "bidirectional"))
    )
    (net (code "122") (name "/DDR3.DQS_P2") (class "Default")
      (node (ref "J6") (pin "25") (pinfunction "DQS2_t_25") (pintype "bidirectional"))
    )
    (net (code "123") (name "/DDR3.DQS_P3") (class "Default")
      (node (ref "J6") (pin "34") (pinfunction "DQS3_t_34") (pintype "bidirectional"))
    )
    (net (code "124") (name "/DDR3.DQS_P4") (class "Default")
      (node (ref "J6") (pin "85") (pinfunction "DQS4_t_85") (pintype "bidirectional"))
    )
    (net (code "125") (name "/DDR3.DQS_P5") (class "Default")
      (node (ref "J6") (pin "94") (pinfunction "DQS5_t_94") (pintype "bidirectional"))
    )
    (net (code "126") (name "/DDR3.DQS_P6") (class "Default")
      (node (ref "J6") (pin "103") (pinfunction "DQS6_t_103") (pintype "bidirectional"))
    )
    (net (code "127") (name "/DDR3.DQS_P7") (class "Default")
      (node (ref "J6") (pin "112") (pinfunction "DQS7_t_112") (pintype "bidirectional"))
    )
    (net (code "128") (name "/DDR3.DQS_P8") (class "Default")
      (node (ref "J6") (pin "43") (pinfunction "DQS8_t_43") (pintype "bidirectional"))
    )
    (net (code "131") (name "/DDR3.ODT0") (class "Default")
      (node (ref "J6") (pin "195") (pinfunction "ODT0_195") (pintype "input"))
    )
    (net (code "132") (name "/DDR3.ODT1") (class "Default")
      (node (ref "J6") (pin "77") (pinfunction "ODT1_77") (pintype "input"))
    )
    (net (code "133") (name "/DDR3.RASn") (class "Default")
      (node (ref "J6") (pin "192") (pinfunction "RAS_n_192") (pintype "input"))
    )
    (net (code "134") (name "/DDR3.RESETn") (class "Default")
      (node (ref "J6") (pin "168") (pinfunction "RESET_n_168") (pintype "input"))
    )
    (net (code "135") (name "/DDR3.Sn0") (class "Default")
      (node (ref "J6") (pin "193") (pinfunction "S0_n_193") (pintype "input"))
    )
    (net (code "136") (name "/DDR3.Sn1") (class "Default")
      (node (ref "J6") (pin "76") (pinfunction "S1_n_76") (pintype "input"))
    )
    (net (code "137") (name "/DDR3.Sn2") (class "Default")
      (node (ref "J6") (pin "79") (pinfunction "S2_n_79") (pintype "input"))
    )
    (net (code "138") (name "/DDR3.Sn3") (class "Default")
      (node (ref "J6") (pin "198") (pinfunction "S3_n_198") (pintype "input"))
    )
    (net (code "140") (name "/DDR3.WEn") (class "Default")
      (node (ref "J6") (pin "73") (pinfunction "WE_n_73") (pintype "input"))
    )
    (net (code "142") (name "/PPC_SCL") (class "Default")
      (node (ref "R378") (pin "2") (pinfunction "2_2") (pintype "passive"))
    )
    (net (code "143") (name "/PPC_SDA") (class "Default")
      (node (ref "R379") (pin "2") (pinfunction "2_2") (pintype "passive"))
    )
    (net (code "145") (name "1V5") (class "Default")
      (node (ref "C632") (pin "1") (pinfunction "1_1") (pintype "passive"))
      (node (ref "C633") (pin "2") (pinfunction "2_2") (pintype "passive"))
      (node (ref "C634") (pin "2") (pinfunction "2_2") (pintype "passive"))
      (node (ref "C635") (pin "2") (pinfunction "2_2") (pintype "passive"))
      (node (ref "C636") (pin "2") (pinfunction "2_2") (pintype "passive"))
      (node (ref "C637") (pin "2") (pinfunction "2_2") (pintype "passive"))
      (node (ref "C638") (pin "2") (pinfunction "2_2") (pintype "passive"))
      (node (ref "C639") (pin "2") (pinfunction "2_2") (pintype "passive"))
      (node (ref "C640") (pin "2") (pinfunction "2_2") (pintype "passive"))
      (node (ref "C641") (pin "2") (pinfunction "2_2") (pintype "passive"))
      (node (ref "C642") (pin "2") (pinfunction "2_2") (pintype "passive"))
      (node (ref "C643") (pin "2") (pinfunction "2_2") (pintype "passive"))
      (node (ref "C644") (pin "2") (pinfunction "2_2") (pintype "passive"))
      (node (ref "C645") (pin "2") (pinfunction "2_2") (pintype "passive"))
      (node (ref "C646") (pin "2") (pinfunction "2_2") (pintype "passive"))
      (node (ref "C647") (pin "2") (pinfunction "2_2") (pintype "passive"))
      (node (ref "C648") (pin "2") (pinfunction "2_2") (pintype "passive"))
      (node (ref "C649") (pin "2") (pinfunction "2_2") (pintype "passive"))
      (node (ref "C650") (pin "2") (pinfunction "2_2") (pintype "passive"))
      (node (ref "C662") (pin "2") (pinfunction "2_2") (pintype "passive"))
      (node (ref "J6") (pin "170") (pinfunction "VDD_170") (pintype "passive"))
      (node (ref "J6") (pin "173") (pinfunction "VDD_173") (pintype "passive"))
      (node (ref "J6") (pin "176") (pinfunction "VDD_176") (pintype "passive"))
      (node (ref "J6") (pin "179") (pinfunction "VDD_179") (pintype "passive"))
      (node (ref "J6") (pin "182") (pinfunction "VDD_182") (pintype "passive"))
      (node (ref "J6") (pin "183") (pinfunction "VDD_183") (pintype "passive"))
      (node (ref "J6") (pin "186") (pinfunction "VDD_186") (pintype "passive"))
      (node (ref "J6") (pin "189") (pinfunction "VDD_189") (pintype "passive"))
      (node (ref "J6") (pin "191") (pinfunction "VDD_191") (pintype "passive"))
      (node (ref "J6") (pin "194") (pinfunction "VDD_194") (pintype "passive"))
      (node (ref "J6") (pin "197") (pinfunction "VDD_197") (pintype "passive"))
      (node (ref "J6") (pin "51") (pinfunction "VDD_51") (pintype "passive"))
      (node (ref "J6") (pin "54") (pinfunction "VDD_54") (pintype "passive"))
      (node (ref "J6") (pin "57") (pinfunction "VDD_57") (pintype "passive"))
      (node (ref "J6") (pin "60") (pinfunction "VDD_60") (pintype "passive"))
      (node (ref "J6") (pin "62") (pinfunction "VDD_62") (pintype "passive"))
      (node (ref "J6") (pin "65") (pinfunction "VDD_65") (pintype "passive"))
      (node (ref "J6") (pin "66") (pinfunction "VDD_66") (pintype "passive"))
      (node (ref "J6") (pin "69") (pinfunction "VDD_69") (pintype "passive"))
      (node (ref "J6") (pin "72") (pinfunction "VDD_72") (pintype "passive"))
      (node (ref "J6") (pin "75") (pinfunction "VDD_75") (pintype "passive"))
      (node (ref "J6") (pin "78") (pinfunction "VDD_78") (pintype "passive"))
      (node (ref "U63") (pin "1") (pinfunction "VDDQSNS_1") (pintype "input"))
      (node (ref "U63") (pin "2") (pinfunction "VLDOIN_2") (pintype "input"))
    )
    (net (code "146") (name "3V3") (class "Default")
      (node (ref "J6") (pin "236") (pinfunction "VDDSPD_236") (pintype "passive"))
      (node (ref "R376") (pin "2") (pinfunction "2_2") (pintype "passive"))
      (node (ref "R377") (pin "2") (pinfunction "2_2") (pintype "passive"))
    )
    (net (code "147") (name "5V") (class "Default")
      (node (ref "C661") (pin "2") (pinfunction "2_2") (pintype "passive"))
      (node (ref "R380") (pin "1") (pinfunction "1_1") (pintype "passive"))
      (node (ref "R382") (pin "1") (pinfunction "1_1") (pintype "passive"))
      (node (ref "U63") (pin "10") (pinfunction "VIN_10") (pintype "input"))
    )
    (net (code "148") (name "DDR3_VREF") (class "Default")
      (node (ref "C663") (pin "2") (pinfunction "2_2") (pintype "passive"))
      (node (ref "C664") (pin "2") (pinfunction "2_2") (pintype "passive"))
      (node (ref "C666") (pin "2") (pinfunction "2_2") (pintype "passive"))
      (node (ref "C669") (pin "2") (pinfunction "2_2") (pintype "passive"))
      (node (ref "C670") (pin "2") (pinfunction "2_2") (pintype "passive"))
      (node (ref "J6") (pin "1") (pinfunction "VREFDQ_1") (pintype "passive"))
      (node (ref "J6") (pin "67") (pinfunction "VREFCA_67") (pintype "passive"))
      (node (ref "U63") (pin "6") (pinfunction "VTTREF_6") (pintype "output"))
    )
    (net (code "149") (name "DDR3_VTT") (class "Default")
      (node (ref "C651") (pin "2") (pinfunction "2_2") (pintype "passive"))
      (node (ref "C652") (pin "2") (pinfunction "2_2") (pintype "passive"))
      (node (ref "C653") (pin "2") (pinfunction "2_2") (pintype "passive"))
      (node (ref "C654") (pin "2") (pinfunction "2_2") (pintype "passive"))
      (node (ref "C655") (pin "2") (pinfunction "2_2") (pintype "passive"))
      (node (ref "C667") (pin "2") (pinfunction "2_2") (pintype "passive"))
      (node (ref "C668") (pin "2") (pinfunction "2_2") (pintype "passive"))
      (node (ref "J6") (pin "120") (pinfunction "VTT_120") (pintype "passive"))
      (node (ref "J6") (pin "240") (pinfunction "VTT_240") (pintype "passive"))
      (node (ref "J6") (pin "48") (pinfunction "VTT_48") (pintype "passive"))
      (node (ref "J6") (pin "49") (pinfunction "VTT_49") (pintype "passive"))
      (node (ref "R381") (pin "1") (pinfunction "1_1") (pintype "passive"))
      (node (ref "U63") (pin "3") (pinfunction "VTT_3") (pintype "output"))
    )
    (net (code "150") (name "GND") (class "Default")
      (node (ref "C632") (pin "2") (pinfunction "2_2") (pintype "passive"))
      (node (ref "C633") (pin "1") (pinfunction "1_1") (pintype "passive"))
      (node (ref "C634") (pin "1") (pinfunction "1_1") (pintype "passive"))
      (node (ref "C635") (pin "1") (pinfunction "1_1") (pintype "passive"))
      (node (ref "C636") (pin "1") (pinfunction "1_1") (pintype "passive"))
      (node (ref "C637") (pin "1") (pinfunction "1_1") (pintype "passive"))
      (node (ref "C638") (pin "1") (pinfunction "1_1") (pintype "passive"))
      (node (ref "C639") (pin "1") (pinfunction "1_1") (pintype "passive"))
      (node (ref "C640") (pin "1") (pinfunction "1_1") (pintype "passive"))
      (node (ref "C641") (pin "1") (pinfunction "1_1") (pintype "passive"))
      (node (ref "C642") (pin "1") (pinfunction "1_1") (pintype "passive"))
      (node (ref "C643") (pin "1") (pinfunction "1_1") (pintype "passive"))
      (node (ref "C644") (pin "1") (pinfunction "1_1") (pintype "passive"))
      (node (ref "C645") (pin "1") (pinfunction "1_1") (pintype "passive"))
      (node (ref "C646") (pin "1") (pinfunction "1_1") (pintype "passive"))
      (node (ref "C647") (pin "1") (pinfunction "1_1") (pintype "passive"))
      (node (ref "C648") (pin "1") (pinfunction "1_1") (pintype "passive"))
      (node (ref "C649") (pin "1") (pinfunction "1_1") (pintype "passive"))
      (node (ref "C650") (pin "1") (pinfunction "1_1") (pintype "passive"))
      (node (ref "C651") (pin "1") (pinfunction "1_1") (pintype "passive"))
      (node (ref "C652") (pin "1") (pinfunction "1_1") (pintype "passive"))
      (node (ref "C653") (pin "1") (pinfunction "1_1") (pintype "passive"))
      (node (ref "C654") (pin "1") (pinfunction "1_1") (pintype "passive"))
      (node (ref "C655") (pin "1") (pinfunction "1_1") (pintype "passive"))
      (node (ref "C661") (pin "1") (pinfunction "1_1") (pintype "passive"))
      (node (ref "C662") (pin "1") (pinfunction "1_1") (pintype "passive"))
      (node (ref "C663") (pin "1") (pinfunction "1_1") (pintype "passive"))
      (node (ref "C664") (pin "1") (pinfunction "1_1") (pintype "passive"))
      (node (ref "C665") (pin "1") (pinfunction "1_1") (pintype "passive"))
      (node (ref "C666") (pin "1") (pinfunction "1_1") (pintype "passive"))
      (node (ref "C667") (pin "1") (pinfunction "1_1") (pintype "passive"))
      (node (ref "C668") (pin "1") (pinfunction "1_1") (pintype "passive"))
      (node (ref "C669") (pin "1") (pinfunction "1_1") (pintype "passive"))
      (node (ref "C670") (pin "1") (pinfunction "1_1") (pintype "passive"))
      (node (ref "J6") (pin "101") (pinfunction "VSS_101") (pintype "passive"))
      (node (ref "J6") (pin "104") (pinfunction "VSS_104") (pintype "passive"))
      (node (ref "J6") (pin "107") (pinfunction "VSS_107") (pintype "passive"))
      (node (ref "J6") (pin "11") (pinfunction "VSS_11") (pintype "passive"))
      (node (ref "J6") (pin "110") (pinfunction "VSS_110") (pintype "passive"))
      (node (ref "J6") (pin "113") (pinfunction "VSS_113") (pintype "passive"))
      (node (ref "J6") (pin "116") (pinfunction "VSS_116") (pintype "passive"))
      (node (ref "J6") (pin "117") (pinfunction "SA0_117") (pintype "input"))
      (node (ref "J6") (pin "119") (pinfunction "SA2_119") (pintype "input"))
      (node (ref "J6") (pin "121") (pinfunction "VSS_121") (pintype "passive"))
      (node (ref "J6") (pin "124") (pinfunction "VSS_124") (pintype "passive"))
      (node (ref "J6") (pin "127") (pinfunction "VSS_127") (pintype "passive"))
      (node (ref "J6") (pin "130") (pinfunction "VSS_130") (pintype "passive"))
      (node (ref "J6") (pin "133") (pinfunction "VSS_133") (pintype "passive"))
      (node (ref "J6") (pin "136") (pinfunction "VSS_136") (pintype "passive"))
      (node (ref "J6") (pin "139") (pinfunction "VSS_139") (pintype "passive"))
      (node (ref "J6") (pin "14") (pinfunction "VSS_14") (pintype "passive"))
      (node (ref "J6") (pin "142") (pinfunction "VSS_142") (pintype "passive"))
      (node (ref "J6") (pin "145") (pinfunction "VSS_145") (pintype "passive"))
      (node (ref "J6") (pin "148") (pinfunction "VSS_148") (pintype "passive"))
      (node (ref "J6") (pin "151") (pinfunction "VSS_151") (pintype "passive"))
      (node (ref "J6") (pin "154") (pinfunction "VSS_154") (pintype "passive"))
      (node (ref "J6") (pin "157") (pinfunction "VSS_157") (pintype "passive"))
      (node (ref "J6") (pin "160") (pinfunction "VSS_160") (pintype "passive"))
      (node (ref "J6") (pin "163") (pinfunction "VSS_163") (pintype "passive"))
      (node (ref "J6") (pin "166") (pinfunction "VSS_166") (pintype "passive"))
      (node (ref "J6") (pin "17") (pinfunction "VSS_17") (pintype "passive"))
      (node (ref "J6") (pin "199") (pinfunction "VSS_199") (pintype "passive"))
      (node (ref "J6") (pin "2") (pinfunction "VSS_2") (pintype "passive"))
      (node (ref "J6") (pin "20") (pinfunction "VSS_20") (pintype "passive"))
      (node (ref "J6") (pin "202") (pinfunction "VSS_202") (pintype "passive"))
      (node (ref "J6") (pin "205") (pinfunction "VSS_205") (pintype "passive"))
      (node (ref "J6") (pin "208") (pinfunction "VSS_208") (pintype "passive"))
      (node (ref "J6") (pin "211") (pinfunction "VSS_211") (pintype "passive"))
      (node (ref "J6") (pin "214") (pinfunction "VSS_214") (pintype "passive"))
      (node (ref "J6") (pin "217") (pinfunction "VSS_217") (pintype "passive"))
      (node (ref "J6") (pin "220") (pinfunction "VSS_220") (pintype "passive"))
      (node (ref "J6") (pin "223") (pinfunction "VSS_223") (pintype "passive"))
      (node (ref "J6") (pin "226") (pinfunction "VSS_226") (pintype "passive"))
      (node (ref "J6") (pin "229") (pinfunction "VSS_229") (pintype "passive"))
      (node (ref "J6") (pin "23") (pinfunction "VSS_23") (pintype "passive"))
      (node (ref "J6") (pin "232") (pinfunction "VSS_232") (pintype "passive"))
      (node (ref "J6") (pin "235") (pinfunction "VSS_235") (pintype "passive"))
      (node (ref "J6") (pin "237") (pinfunction "SA1_237") (pintype "input"))
      (node (ref "J6") (pin "239") (pinfunction "VSS_239") (pintype "passive"))
      (node (ref "J6") (pin "26") (pinfunction "VSS_26") (pintype "passive"))
      (node (ref "J6") (pin "29") (pinfunction "VSS_29") (pintype "passive"))
      (node (ref "J6") (pin "32") (pinfunction "VSS_32") (pintype "passive"))
      (node (ref "J6") (pin "35") (pinfunction "VSS_35") (pintype "passive"))
      (node (ref "J6") (pin "38") (pinfunction "VSS_38") (pintype "passive"))
      (node (ref "J6") (pin "41") (pinfunction "VSS_41") (pintype "passive"))
      (node (ref "J6") (pin "44") (pinfunction "VSS_44") (pintype "passive"))
      (node (ref "J6") (pin "47") (pinfunction "VSS_47") (pintype "passive"))
      (node (ref "J6") (pin "5") (pinfunction "VSS_5") (pintype "passive"))
      (node (ref "J6") (pin "8") (pinfunction "VSS_8") (pintype "passive"))
      (node (ref "J6") (pin "80") (pinfunction "VSS_80") (pintype "passive"))
      (node (ref "J6") (pin "83") (pinfunction "VSS_83") (pintype "passive"))
      (node (ref "J6") (pin "86") (pinfunction "VSS_86") (pintype "passive"))
      (node (ref "J6") (pin "89") (pinfunction "VSS_89") (pintype "passive"))
      (node (ref "J6") (pin "92") (pinfunction "VSS_92") (pintype "passive"))
      (node (ref "J6") (pin "95") (pinfunction "VSS_95") (pintype "passive"))
      (node (ref "J6") (pin "98") (pinfunction "VSS_98") (pintype "passive"))
      (node (ref "U63") (pin "11") (pinfunction "PPAD_11") (pintype "passive"))
      (node (ref "U63") (pin "4") (pinfunction "PGND_4") (pintype "passive"))
      (node (ref "U63") (pin "8") (pinfunction "GND_8") (pintype "passive"))
    )
    (net (code "151") (name "Net-(J6B-CK1_c)") (class "Default")
      (node (ref "J6") (pin "64") (pinfunction "CK1_c_64") (pintype "input"))
      (node (ref "TP25") (pin "1") (pinfunction "1_1") (pintype "passive"))
    )
    (net (code "152") (name "Net-(J6B-CK1_t)") (class "Default")
      (node (ref "J6") (pin "63") (pinfunction "CK1_t_63") (pintype "input"))
      (node (ref "TP24") (pin "1") (pinfunction "1_1") (pintype "passive"))
    )
    (net (code "153") (name "Net-(J6B-EVENT_n)") (class "Default")
      (node (ref "J6") (pin "187") (pinfunction "EVENT_n_187") (pintype "output"))
      (node (ref "TP30") (pin "1") (pinfunction "1_1") (pintype "passive"))
    )
    (net (code "154") (name "Net-(J6B-Err_Out_n)") (class "Default")
      (node (ref "J6") (pin "53") (pinfunction "Err_Out_n_53") (pintype "output"))
      (node (ref "TP27") (pin "1") (pinfunction "1_1") (pintype "passive"))
    )
    (net (code "155") (name "Net-(J6B-Par_In)") (class "Default")
      (node (ref "J6") (pin "68") (pinfunction "Par_In_68") (pintype "input"))
      (node (ref "TP26") (pin "1") (pinfunction "1_1") (pintype "passive"))
    )
    (net (code "156") (name "Net-(J6B-SCL)") (class "Default")
      (node (ref "J6") (pin "118") (pinfunction "SCL_118") (pintype "input"))
      (node (ref "R377") (pin "1") (pinfunction "1_1") (pintype "passive"))
      (node (ref "R378") (pin "1") (pinfunction "1_1") (pintype "passive"))
    )
    (net (code "157") (name "Net-(J6B-SDA)") (class "Default")
      (node (ref "J6") (pin "238") (pinfunction "SDA_238") (pintype "input"))
      (node (ref "R376") (pin "1") (pinfunction "1_1") (pintype "passive"))
      (node (ref "R379") (pin "1") (pinfunction "1_1") (pintype "passive"))
    )
    (net (code "158") (name "Net-(U63-S3)") (class "Default")
      (node (ref "R380") (pin "2") (pinfunction "2_2") (pintype "passive"))
      (node (ref "U63") (pin "7") (pinfunction "S3_7") (pintype "input"))
    )
    (net (code "159") (name "Net-(U63-S5)") (class "Default")
      (node (ref "R382") (pin "2") (pinfunction "2_2") (pintype "passive"))
      (node (ref "U63") (pin "9") (pinfunction "S5_9") (pintype "input"))
    )
    (net (code "160") (name "Net-(U63-VTTSNS)") (class "Default")
      (node (ref "C665") (pin "2") (pinfunction "2_2") (pintype "passive"))
      (node (ref "R381") (pin "2") (pinfunction "2_2") (pintype "passive"))
      (node (ref "U63") (pin "5") (pinfunction "VTTSNS_5") (pintype "input"))
    )
    (net (code "161") (name "unconnected-(J6B-TEST-Pad167)") (class "Default")
      (node (ref "J6") (pin "167") (pinfunction "TEST_167") (pintype "output+no_connect"))
    )
    (net (code "162") (name "unconnected-(J6E-NC-Pad126)") (class "Default")
      (node (ref "J6") (pin "126") (pinfunction "NC_126") (pintype "passive+no_connect"))
    )
    (net (code "163") (name "unconnected-(J6E-NC-Pad135)") (class "Default")
      (node (ref "J6") (pin "135") (pinfunction "NC_135") (pintype "passive+no_connect"))
    )
    (net (code "164") (name "unconnected-(J6E-NC-Pad144)") (class "Default")
      (node (ref "J6") (pin "144") (pinfunction "NC_144") (pintype "passive+no_connect"))
    )
    (net (code "165") (name "unconnected-(J6E-NC-Pad153)") (class "Default")
      (node (ref "J6") (pin "153") (pinfunction "NC_153") (pintype "passive+no_connect"))
    )
    (net (code "166") (name "unconnected-(J6E-NC-Pad162)") (class "Default")
      (node (ref "J6") (pin "162") (pinfunction "NC_162") (pintype "passive+no_connect"))
    )
    (net (code "167") (name "unconnected-(J6E-NC-Pad204)") (class "Default")
      (node (ref "J6") (pin "204") (pinfunction "NC_204") (pintype "passive+no_connect"))
    )
    (net (code "168") (name "unconnected-(J6E-NC-Pad213)") (class "Default")
      (node (ref "J6") (pin "213") (pinfunction "NC_213") (pintype "passive+no_connect"))
    )
    (net (code "169") (name "unconnected-(J6E-NC-Pad222)") (class "Default")
      (node (ref "J6") (pin "222") (pinfunction "NC_222") (pintype "passive+no_connect"))
    )
    (net (code "170") (name "unconnected-(J6E-NC-Pad231)") (class "Default")
      (node (ref "J6") (pin "231") (pinfunction "NC_231") (pintype "passive+no_connect"))
    )
  )
)
